# MB_RELAY.net
KiCad netlist of a schematic drawn in Altium Designer
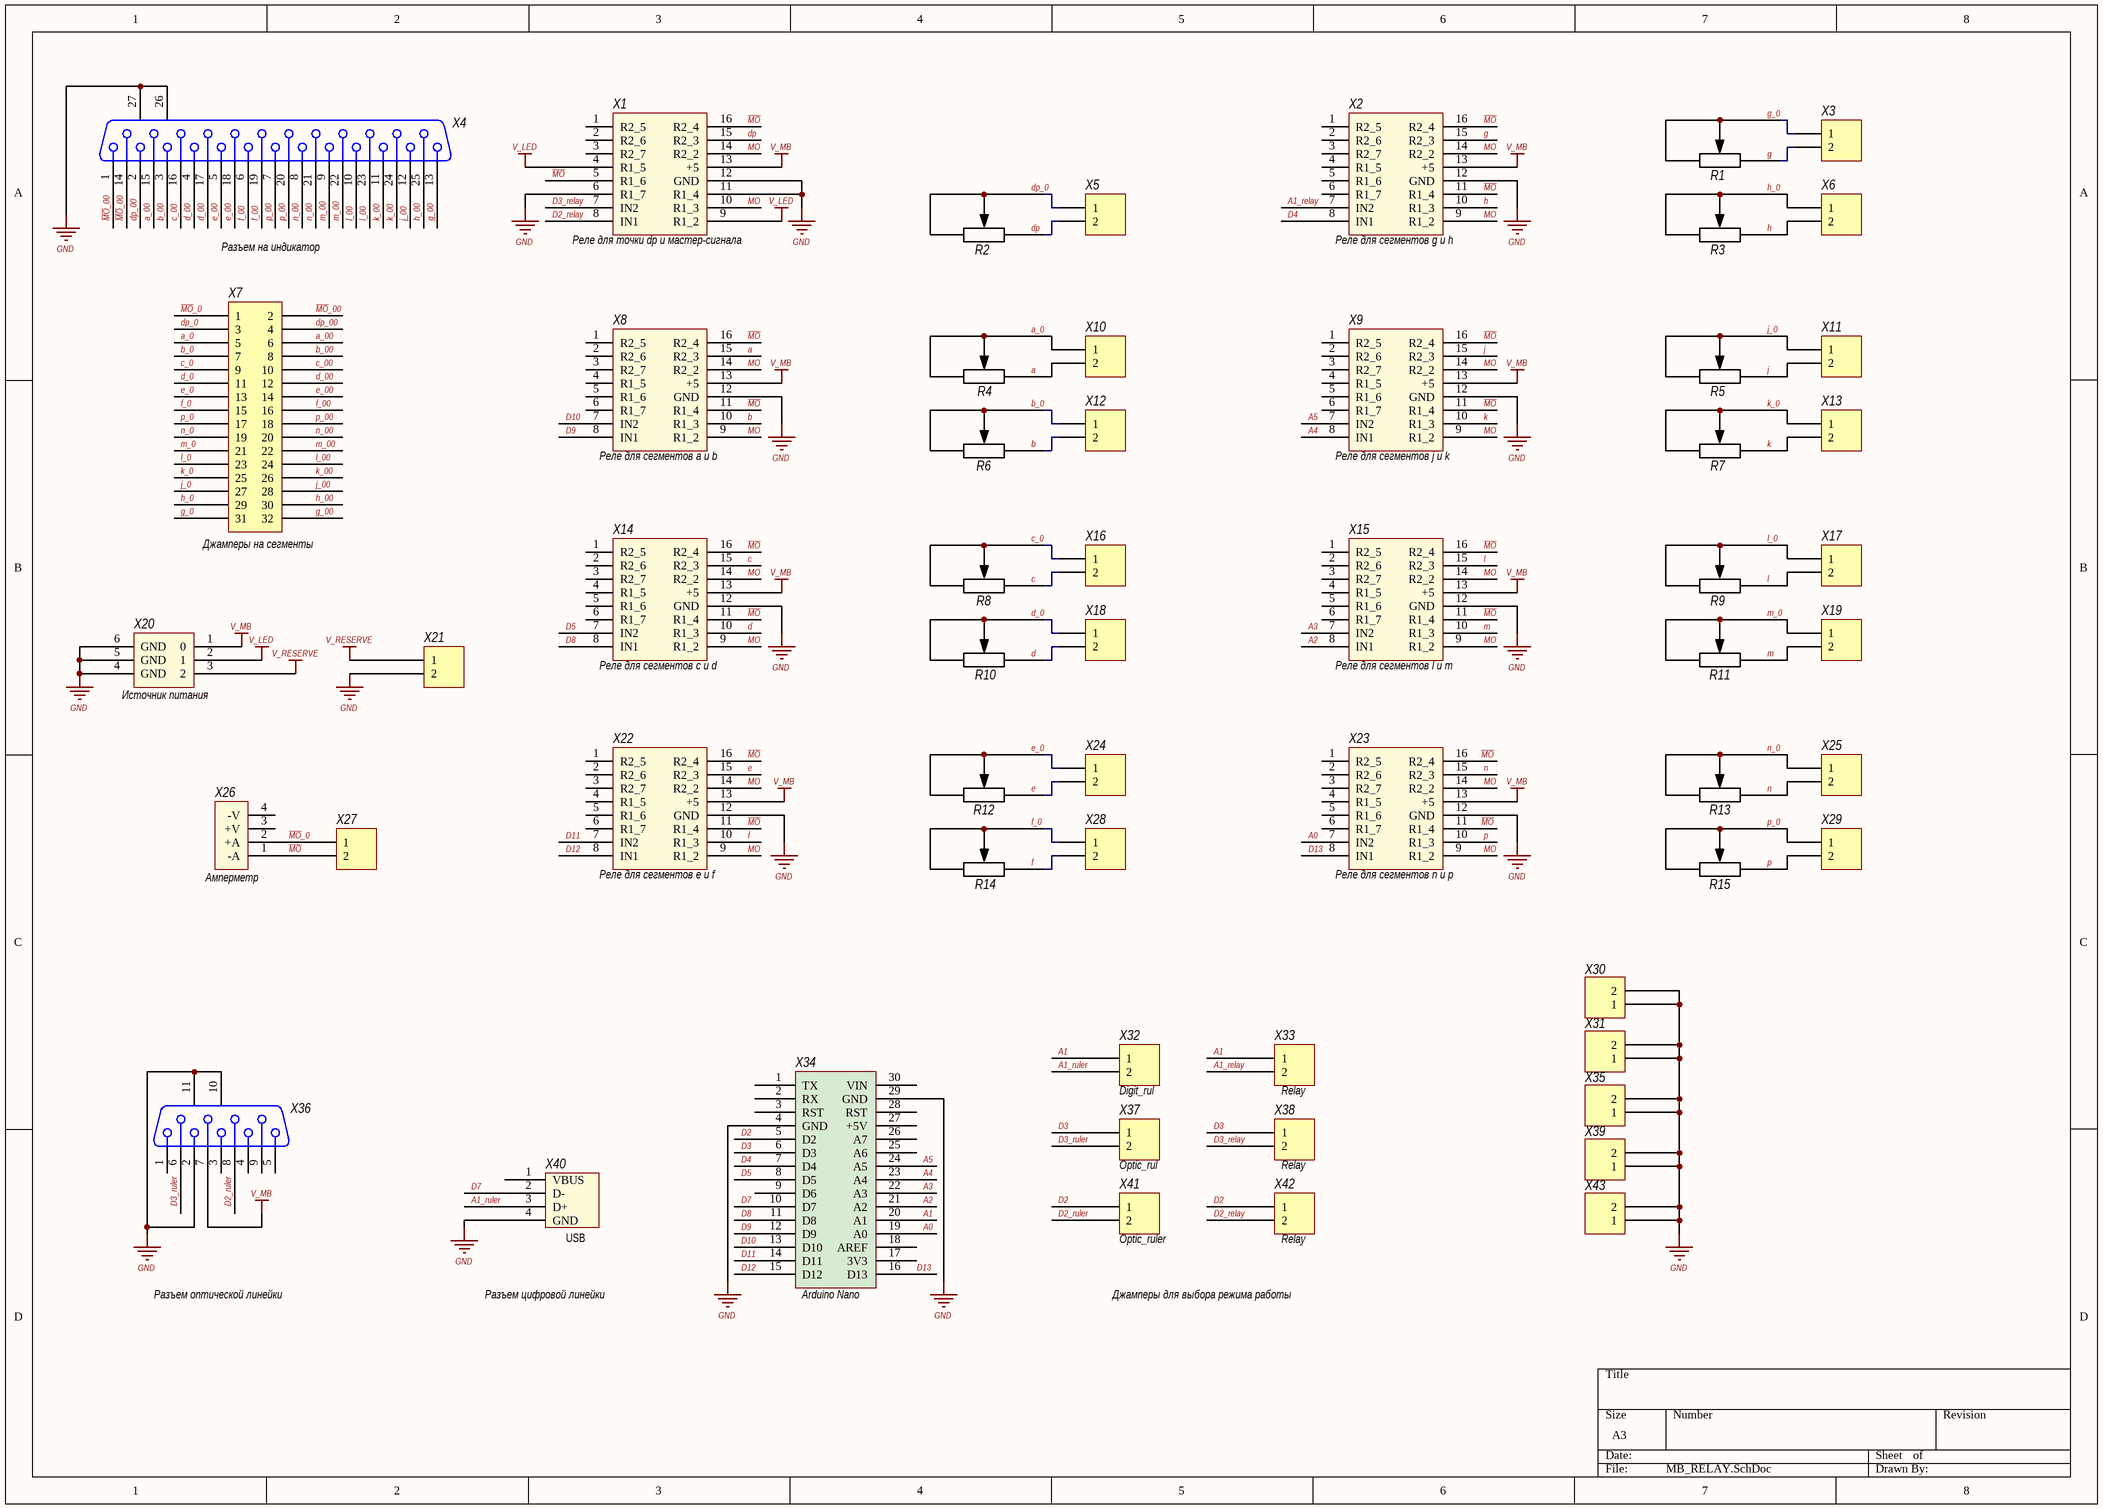
[diagram p0: MB_RELAY.SchDoc]

(export (version "E")
  (design (tool "Eeschema 10.0.6"))
  (components
    (comp (ref "R1")
      (value "RES 3266W")
      (footprint "aab_Passive:RES 3266W")
      (libsource (lib "aab_Schlib") (part "RES 3266W"))
    )
    (comp (ref "R2")
      (value "RES 3266W")
      (footprint "aab_Passive:RES 3266W")
      (libsource (lib "aab_Schlib") (part "RES 3266W"))
    )
    (comp (ref "R3")
      (value "RES 3266W")
      (footprint "aab_Passive:RES 3266W")
      (libsource (lib "aab_Schlib") (part "RES 3266W"))
    )
    (comp (ref "R4")
      (value "Переменнный резистор для")
      (footprint "aab_Passive:RES 3266W")
      (libsource (lib "aab_Schlib") (part "RES 3266W"))
    )
    (comp (ref "R5")
      (value "RES 3266W")
      (footprint "aab_Passive:RES 3266W")
      (libsource (lib "aab_Schlib") (part "RES 3266W"))
    )
    (comp (ref "R6")
      (value "RES 3266W")
      (footprint "aab_Passive:RES 3266W")
      (libsource (lib "aab_Schlib") (part "RES 3266W"))
    )
    (comp (ref "R7")
      (value "RES 3266W")
      (footprint "aab_Passive:RES 3266W")
      (libsource (lib "aab_Schlib") (part "RES 3266W"))
    )
    (comp (ref "R8")
      (value "RES 3266W")
      (footprint "aab_Passive:RES 3266W")
      (libsource (lib "aab_Schlib") (part "RES 3266W"))
    )
    (comp (ref "R9")
      (value "RES 3266W")
      (footprint "aab_Passive:RES 3266W")
      (libsource (lib "aab_Schlib") (part "RES 3266W"))
    )
    (comp (ref "R10")
      (value "RES 3266W")
      (footprint "aab_Passive:RES 3266W")
      (libsource (lib "aab_Schlib") (part "RES 3266W"))
    )
    (comp (ref "R11")
      (value "RES 3266W")
      (footprint "aab_Passive:RES 3266W")
      (libsource (lib "aab_Schlib") (part "RES 3266W"))
    )
    (comp (ref "R12")
      (value "RES 3266W")
      (footprint "aab_Passive:RES 3266W")
      (libsource (lib "aab_Schlib") (part "RES 3266W"))
    )
    (comp (ref "R13")
      (value "RES 3266W")
      (footprint "aab_Passive:RES 3266W")
      (libsource (lib "aab_Schlib") (part "RES 3266W"))
    )
    (comp (ref "R14")
      (value "RES 3266W")
      (footprint "aab_Passive:RES 3266W")
      (libsource (lib "aab_Schlib") (part "RES 3266W"))
    )
    (comp (ref "R15")
      (value "RES 3266W")
      (footprint "aab_Passive:RES 3266W")
      (libsource (lib "aab_Schlib") (part "RES 3266W"))
    )
    (comp (ref "X1")
      (value "Реле для точки dp и мастер-сигнала")
      (footprint "MEZ_RELAY")
      (libsource (lib "msp_SchLib") (part "MEZ_RELAY"))
    )
    (comp (ref "X2")
      (value "Реле для сегментов g и h")
      (footprint "MEZ_RELAY")
      (libsource (lib "msp_SchLib") (part "MEZ_RELAY"))
    )
    (comp (ref "X3")
      (value "GND")
      (footprint "HDR1X2")
      (description "Header, 2-Pin")
      (fields (field (name "PUBLISHER") "Altium Limited"))
      (libsource (lib "Miscellaneous Connectors") (part "Header 2"))
    )
    (comp (ref "X4")
      (value "D Connector 25")
      (footprint "DSUB1.385-2H25A")
      (description "Receptacle Assembly, 25 Position, Right Angle")
      (fields (field (name "PUBLISHER") "Altium Limited"))
      (libsource (lib "Miscellaneous Connectors") (part "D Connector 25"))
    )
    (comp (ref "X5")
      (value "GND")
      (footprint "HDR1X2")
      (description "Header, 2-Pin")
      (fields (field (name "PUBLISHER") "Altium Limited"))
      (libsource (lib "Miscellaneous Connectors") (part "Header 2"))
    )
    (comp (ref "X6")
      (value "GND")
      (footprint "HDR1X2")
      (description "Header, 2-Pin")
      (fields (field (name "PUBLISHER") "Altium Limited"))
      (libsource (lib "Miscellaneous Connectors") (part "Header 2"))
    )
    (comp (ref "X7")
      (value "Header 16X2")
      (footprint "HDR2X16")
      (description "Header, 16-Pin, Dual row")
      (fields (field (name "PUBLISHER") "Altium Limited"))
      (libsource (lib "Miscellaneous Connectors") (part "Header 16X2"))
    )
    (comp (ref "X8")
      (value "Реле для сегментов a и b")
      (footprint "MEZ_RELAY")
      (libsource (lib "msp_SchLib") (part "MEZ_RELAY"))
    )
    (comp (ref "X9")
      (value "Реле для сегментов j и k")
      (footprint "MEZ_RELAY")
      (libsource (lib "msp_SchLib") (part "MEZ_RELAY"))
    )
    (comp (ref "X10")
      (value "Header 2")
      (footprint "HDR1X2")
      (description "Header, 2-Pin")
      (fields (field (name "PUBLISHER") "Altium Limited"))
      (libsource (lib "Miscellaneous Connectors") (part "Header 2"))
    )
    (comp (ref "X11")
      (value "Header 2")
      (footprint "HDR1X2")
      (description "Header, 2-Pin")
      (fields (field (name "PUBLISHER") "Altium Limited"))
      (libsource (lib "Miscellaneous Connectors") (part "Header 2"))
    )
    (comp (ref "X12")
      (value "Header 2")
      (footprint "HDR1X2")
      (description "Header, 2-Pin")
      (fields (field (name "PUBLISHER") "Altium Limited"))
      (libsource (lib "Miscellaneous Connectors") (part "Header 2"))
    )
    (comp (ref "X13")
      (value "Header 2")
      (footprint "HDR1X2")
      (description "Header, 2-Pin")
      (fields (field (name "PUBLISHER") "Altium Limited"))
      (libsource (lib "Miscellaneous Connectors") (part "Header 2"))
    )
    (comp (ref "X14")
      (value "Реле для сегментов c и d")
      (footprint "MEZ_RELAY")
      (libsource (lib "msp_SchLib") (part "MEZ_RELAY"))
    )
    (comp (ref "X15")
      (value "Реле для сегментов l и m")
      (footprint "MEZ_RELAY")
      (libsource (lib "msp_SchLib") (part "MEZ_RELAY"))
    )
    (comp (ref "X16")
      (value "Header 2")
      (footprint "HDR1X2")
      (description "Header, 2-Pin")
      (fields (field (name "PUBLISHER") "Altium Limited"))
      (libsource (lib "Miscellaneous Connectors") (part "Header 2"))
    )
    (comp (ref "X17")
      (value "GND")
      (footprint "HDR1X2")
      (description "Header, 2-Pin")
      (fields (field (name "PUBLISHER") "Altium Limited"))
      (libsource (lib "Miscellaneous Connectors") (part "Header 2"))
    )
    (comp (ref "X18")
      (value "Header 2")
      (footprint "HDR1X2")
      (description "Header, 2-Pin")
      (fields (field (name "PUBLISHER") "Altium Limited"))
      (libsource (lib "Miscellaneous Connectors") (part "Header 2"))
    )
    (comp (ref "X19")
      (value "GND")
      (footprint "HDR1X2")
      (description "Header, 2-Pin")
      (fields (field (name "PUBLISHER") "Altium Limited"))
      (libsource (lib "Miscellaneous Connectors") (part "Header 2"))
    )
    (comp (ref "X20")
      (value "Источник питания")
      (footprint "vpl_Passive:POWER")
      (libsource (lib "msp_SchLib") (part "POWER"))
    )
    (comp (ref "X21")
      (value "Header 2")
      (footprint "HDR1X2")
      (description "Header, 2-Pin")
      (fields (field (name "PUBLISHER") "Altium Limited"))
      (libsource (lib "Miscellaneous Connectors") (part "Header 2"))
    )
    (comp (ref "X22")
      (value "Реле для сегментов e и f")
      (footprint "MEZ_RELAY")
      (libsource (lib "msp_SchLib") (part "MEZ_RELAY"))
    )
    (comp (ref "X23")
      (value "Реле для сегментов n и p")
      (footprint "MEZ_RELAY")
      (libsource (lib "msp_SchLib") (part "MEZ_RELAY"))
    )
    (comp (ref "X24")
      (value "GND")
      (footprint "HDR1X2")
      (description "Header, 2-Pin")
      (fields (field (name "PUBLISHER") "Altium Limited"))
      (libsource (lib "Miscellaneous Connectors") (part "Header 2"))
    )
    (comp (ref "X25")
      (value "GND")
      (footprint "HDR1X2")
      (description "Header, 2-Pin")
      (fields (field (name "PUBLISHER") "Altium Limited"))
      (libsource (lib "Miscellaneous Connectors") (part "Header 2"))
    )
    (comp (ref "X26")
      (value "Амперметр")
      (footprint "vpl_Passive:AMP_VOLTMETER")
      (libsource (lib "msp_SchLib") (part "AMP_VOLTMETR"))
    )
    (comp (ref "X27")
      (value "Header 2")
      (footprint "HDR1X2")
      (description "Header, 2-Pin")
      (fields (field (name "PUBLISHER") "Altium Limited"))
      (libsource (lib "Miscellaneous Connectors") (part "Header 2"))
    )
    (comp (ref "X28")
      (value "GND")
      (footprint "HDR1X2")
      (description "Header, 2-Pin")
      (fields (field (name "PUBLISHER") "Altium Limited"))
      (libsource (lib "Miscellaneous Connectors") (part "Header 2"))
    )
    (comp (ref "X29")
      (value "GND")
      (footprint "HDR1X2")
      (description "Header, 2-Pin")
      (fields (field (name "PUBLISHER") "Altium Limited"))
      (libsource (lib "Miscellaneous Connectors") (part "Header 2"))
    )
    (comp (ref "X30")
      (value "Header 2")
      (footprint "HDR1X2")
      (description "Header, 2-Pin")
      (fields (field (name "PUBLISHER") "Altium Limited"))
      (libsource (lib "") (part "Header 2_1"))
    )
    (comp (ref "X31")
      (value "GND")
      (footprint "HDR1X2")
      (description "Header, 2-Pin")
      (fields (field (name "PUBLISHER") "Altium Limited"))
      (libsource (lib "") (part "Header 2_1"))
    )
    (comp (ref "X32")
      (value "Digit_rul")
      (footprint "HDR1X2")
      (description "Header, 2-Pin")
      (fields (field (name "PUBLISHER") "Altium Limited"))
      (libsource (lib "Miscellaneous Connectors") (part "Header 2"))
    )
    (comp (ref "X33")
      (value "Relay")
      (footprint "HDR1X2")
      (description "Header, 2-Pin")
      (fields (field (name "PUBLISHER") "Altium Limited"))
      (libsource (lib "Miscellaneous Connectors") (part "Header 2"))
    )
    (comp (ref "X34")
      (value "Arduino Nano")
      (footprint "PCBComponent_1")
      (libsource (lib "Nano") (part "Component_1"))
    )
    (comp (ref "X35")
      (value "GND")
      (footprint "HDR1X2")
      (description "Header, 2-Pin")
      (fields (field (name "PUBLISHER") "Altium Limited"))
      (libsource (lib "") (part "Header 2_1"))
    )
    (comp (ref "X36")
      (value "D Connector 9")
      (footprint "DSUB1.385-2H9")
      (description "Receptacle Assembly, 9 Position, Right Angle")
      (fields (field (name "PUBLISHER") "Altium Limited"))
      (libsource (lib "Miscellaneous Connectors") (part "D Connector 9"))
    )
    (comp (ref "X37")
      (value "Optic_rul")
      (footprint "HDR1X2")
      (description "Header, 2-Pin")
      (fields (field (name "PUBLISHER") "Altium Limited"))
      (libsource (lib "Miscellaneous Connectors") (part "Header 2"))
    )
    (comp (ref "X38")
      (value "Relay")
      (footprint "HDR1X2")
      (description "Header, 2-Pin")
      (fields (field (name "PUBLISHER") "Altium Limited"))
      (libsource (lib "Miscellaneous Connectors") (part "Header 2"))
    )
    (comp (ref "X39")
      (value "GND")
      (footprint "HDR1X2")
      (description "Header, 2-Pin")
      (fields (field (name "PUBLISHER") "Altium Limited"))
      (libsource (lib "") (part "Header 2_1"))
    )
    (comp (ref "X40") (value "USB") (footprint "USB") (libsource (lib "msp_SchLib") (part "USB")))
    (comp (ref "X41")
      (value "Optic_ruler")
      (footprint "HDR1X2")
      (description "Header, 2-Pin")
      (fields (field (name "PUBLISHER") "Altium Limited"))
      (libsource (lib "Miscellaneous Connectors") (part "Header 2"))
    )
    (comp (ref "X42")
      (value "Relay")
      (footprint "HDR1X2")
      (description "Header, 2-Pin")
      (fields (field (name "PUBLISHER") "Altium Limited"))
      (libsource (lib "Miscellaneous Connectors") (part "Header 2"))
    )
    (comp (ref "X43")
      (value "GND")
      (footprint "HDR1X2")
      (description "Header, 2-Pin")
      (fields (field (name "PUBLISHER") "Altium Limited"))
      (libsource (lib "") (part "Header 2_1"))
    )
  )
  (nets
    (net (code "1") (name "/A0") (class "Default")
      (node (ref "X23") (pin "7") (pinfunction "IN2_7") (pintype "passive"))
      (node (ref "X34") (pin "19") (pinfunction "A0_19") (pintype "passive"))
    )
    (net (code "2") (name "/A1") (class "Default")
      (node (ref "X32") (pin "1") (pinfunction "1_1") (pintype "passive"))
      (node (ref "X33") (pin "1") (pinfunction "1_1") (pintype "passive"))
      (node (ref "X34") (pin "20") (pinfunction "A1_20") (pintype "passive"))
    )
    (net (code "3") (name "/A1_relay") (class "Default")
      (node (ref "X2") (pin "7") (pinfunction "IN2_7") (pintype "passive"))
      (node (ref "X33") (pin "2") (pinfunction "2_2") (pintype "passive"))
    )
    (net (code "4") (name "/A1_ruler") (class "Default")
      (node (ref "X32") (pin "2") (pinfunction "2_2") (pintype "passive"))
      (node (ref "X40") (pin "3") (pinfunction "D+_3") (pintype "passive"))
    )
    (net (code "5") (name "/A2") (class "Default")
      (node (ref "X15") (pin "8") (pinfunction "IN1_8") (pintype "passive"))
      (node (ref "X34") (pin "21") (pinfunction "A2_21") (pintype "passive"))
    )
    (net (code "6") (name "/A3") (class "Default")
      (node (ref "X15") (pin "7") (pinfunction "IN2_7") (pintype "passive"))
      (node (ref "X34") (pin "22") (pinfunction "A3_22") (pintype "passive"))
    )
    (net (code "7") (name "/A4") (class "Default")
      (node (ref "X34") (pin "23") (pinfunction "A4_23") (pintype "passive"))
      (node (ref "X9") (pin "8") (pinfunction "IN1_8") (pintype "passive"))
    )
    (net (code "8") (name "/A5") (class "Default")
      (node (ref "X34") (pin "24") (pinfunction "A5_24") (pintype "passive"))
      (node (ref "X9") (pin "7") (pinfunction "IN2_7") (pintype "passive"))
    )
    (net (code "9") (name "/D2") (class "Default")
      (node (ref "X34") (pin "5") (pinfunction "D2_5") (pintype "passive"))
      (node (ref "X41") (pin "1") (pinfunction "1_1") (pintype "passive"))
      (node (ref "X42") (pin "1") (pinfunction "1_1") (pintype "passive"))
    )
    (net (code "10") (name "/D2_relay") (class "Default")
      (node (ref "X1") (pin "8") (pinfunction "IN1_8") (pintype "passive"))
      (node (ref "X42") (pin "2") (pinfunction "2_2") (pintype "passive"))
    )
    (net (code "11") (name "/D2_ruler") (class "Default")
      (node (ref "X36") (pin "8") (pinfunction "8_8") (pintype "passive"))
      (node (ref "X41") (pin "2") (pinfunction "2_2") (pintype "passive"))
    )
    (net (code "12") (name "/D3") (class "Default")
      (node (ref "X34") (pin "6") (pinfunction "D3_6") (pintype "passive"))
      (node (ref "X37") (pin "1") (pinfunction "1_1") (pintype "passive"))
      (node (ref "X38") (pin "1") (pinfunction "1_1") (pintype "passive"))
    )
    (net (code "13") (name "/D3_relay") (class "Default")
      (node (ref "X1") (pin "7") (pinfunction "IN2_7") (pintype "passive"))
      (node (ref "X38") (pin "2") (pinfunction "2_2") (pintype "passive"))
    )
    (net (code "14") (name "/D3_ruler") (class "Default")
      (node (ref "X36") (pin "6") (pinfunction "6_6") (pintype "passive"))
      (node (ref "X37") (pin "2") (pinfunction "2_2") (pintype "passive"))
    )
    (net (code "15") (name "/D4") (class "Default")
      (node (ref "X2") (pin "8") (pinfunction "IN1_8") (pintype "passive"))
      (node (ref "X34") (pin "7") (pinfunction "D4_7") (pintype "passive"))
    )
    (net (code "16") (name "/D5") (class "Default")
      (node (ref "X14") (pin "7") (pinfunction "IN2_7") (pintype "passive"))
      (node (ref "X34") (pin "8") (pinfunction "D5_8") (pintype "passive"))
    )
    (net (code "17") (name "/D7") (class "Default")
      (node (ref "X34") (pin "10") (pinfunction "D7_10") (pintype "passive"))
      (node (ref "X40") (pin "2") (pinfunction "D-_2") (pintype "passive"))
    )
    (net (code "18") (name "/D8") (class "Default")
      (node (ref "X14") (pin "8") (pinfunction "IN1_8") (pintype "passive"))
      (node (ref "X34") (pin "11") (pinfunction "D8_11") (pintype "passive"))
    )
    (net (code "19") (name "/D9") (class "Default")
      (node (ref "X34") (pin "12") (pinfunction "D9_12") (pintype "passive"))
      (node (ref "X8") (pin "8") (pinfunction "IN1_8") (pintype "passive"))
    )
    (net (code "20") (name "/D10") (class "Default")
      (node (ref "X34") (pin "13") (pinfunction "D10_13") (pintype "passive"))
      (node (ref "X8") (pin "7") (pinfunction "IN2_7") (pintype "passive"))
    )
    (net (code "21") (name "/D11") (class "Default")
      (node (ref "X22") (pin "7") (pinfunction "IN2_7") (pintype "passive"))
      (node (ref "X34") (pin "14") (pinfunction "D11_14") (pintype "passive"))
    )
    (net (code "22") (name "/D12") (class "Default")
      (node (ref "X22") (pin "8") (pinfunction "IN1_8") (pintype "passive"))
      (node (ref "X34") (pin "15") (pinfunction "D12_15") (pintype "passive"))
    )
    (net (code "23") (name "/D13") (class "Default")
      (node (ref "X23") (pin "8") (pinfunction "IN1_8") (pintype "passive"))
      (node (ref "X34") (pin "16") (pinfunction "D13_16") (pintype "passive"))
    )
    (net (code "24") (name "/MO") (class "Default")
      (node (ref "X1") (pin "10") (pinfunction "R1_3_10") (pintype "passive"))
      (node (ref "X1") (pin "14") (pinfunction "R2_2_14") (pintype "passive"))
      (node (ref "X14") (pin "14") (pinfunction "R2_2_14") (pintype "passive"))
      (node (ref "X14") (pin "9") (pinfunction "R1_2_9") (pintype "passive"))
      (node (ref "X15") (pin "14") (pinfunction "R2_2_14") (pintype "passive"))
      (node (ref "X15") (pin "9") (pinfunction "R1_2_9") (pintype "passive"))
      (node (ref "X2") (pin "14") (pinfunction "R2_2_14") (pintype "passive"))
      (node (ref "X2") (pin "9") (pinfunction "R1_2_9") (pintype "passive"))
      (node (ref "X22") (pin "14") (pinfunction "R2_2_14") (pintype "passive"))
      (node (ref "X22") (pin "9") (pinfunction "R1_2_9") (pintype "passive"))
      (node (ref "X23") (pin "14") (pinfunction "R2_2_14") (pintype "passive"))
      (node (ref "X23") (pin "9") (pinfunction "R1_2_9") (pintype "passive"))
      (node (ref "X8") (pin "14") (pinfunction "R2_2_14") (pintype "passive"))
      (node (ref "X8") (pin "9") (pinfunction "R1_2_9") (pintype "passive"))
      (node (ref "X9") (pin "14") (pinfunction "R2_2_14") (pintype "passive"))
      (node (ref "X9") (pin "9") (pinfunction "R1_2_9") (pintype "passive"))
    )
    (net (code "25") (name "/a") (class "Default")
      (node (ref "R4") (pin "3") (pinfunction "3_3") (pintype "passive"))
      (node (ref "X10") (pin "2") (pinfunction "2_2") (pintype "passive"))
      (node (ref "X8") (pin "15") (pinfunction "R2_3_15") (pintype "passive"))
    )
    (net (code "26") (name "/a_00") (class "Default")
      (node (ref "X4") (pin "15") (pinfunction "15_15") (pintype "passive"))
      (node (ref "X7") (pin "6") (pinfunction "6_6") (pintype "passive"))
    )
    (net (code "27") (name "/a_0") (class "Default")
      (node (ref "R4") (pin "1") (pinfunction "1_1") (pintype "passive"))
      (node (ref "R4") (pin "2") (pinfunction "2_2") (pintype "passive"))
      (node (ref "X10") (pin "1") (pinfunction "1_1") (pintype "passive"))
      (node (ref "X7") (pin "5") (pinfunction "5_5") (pintype "passive"))
    )
    (net (code "28") (name "/b") (class "Default")
      (node (ref "R6") (pin "3") (pinfunction "3_3") (pintype "passive"))
      (node (ref "X12") (pin "2") (pinfunction "2_2") (pintype "passive"))
      (node (ref "X8") (pin "10") (pinfunction "R1_3_10") (pintype "passive"))
    )
    (net (code "29") (name "/b_00") (class "Default")
      (node (ref "X4") (pin "3") (pinfunction "3_3") (pintype "passive"))
      (node (ref "X7") (pin "8") (pinfunction "8_8") (pintype "passive"))
    )
    (net (code "30") (name "/b_0") (class "Default")
      (node (ref "R6") (pin "1") (pinfunction "1_1") (pintype "passive"))
      (node (ref "R6") (pin "2") (pinfunction "2_2") (pintype "passive"))
      (node (ref "X12") (pin "1") (pinfunction "1_1") (pintype "passive"))
      (node (ref "X7") (pin "7") (pinfunction "7_7") (pintype "passive"))
    )
    (net (code "31") (name "/c") (class "Default")
      (node (ref "R8") (pin "3") (pinfunction "3_3") (pintype "passive"))
      (node (ref "X14") (pin "15") (pinfunction "R2_3_15") (pintype "passive"))
      (node (ref "X16") (pin "2") (pinfunction "2_2") (pintype "passive"))
    )
    (net (code "32") (name "/c_00") (class "Default")
      (node (ref "X4") (pin "16") (pinfunction "16_16") (pintype "passive"))
      (node (ref "X7") (pin "10") (pinfunction "10_10") (pintype "passive"))
    )
    (net (code "33") (name "/c_0") (class "Default")
      (node (ref "R8") (pin "1") (pinfunction "1_1") (pintype "passive"))
      (node (ref "R8") (pin "2") (pinfunction "2_2") (pintype "passive"))
      (node (ref "X16") (pin "1") (pinfunction "1_1") (pintype "passive"))
      (node (ref "X7") (pin "9") (pinfunction "9_9") (pintype "passive"))
    )
    (net (code "34") (name "/d") (class "Default")
      (node (ref "R10") (pin "3") (pinfunction "3_3") (pintype "passive"))
      (node (ref "X14") (pin "10") (pinfunction "R1_3_10") (pintype "passive"))
      (node (ref "X18") (pin "2") (pinfunction "2_2") (pintype "passive"))
    )
    (net (code "35") (name "/d_0") (class "Default")
      (node (ref "R10") (pin "1") (pinfunction "1_1") (pintype "passive"))
      (node (ref "R10") (pin "2") (pinfunction "2_2") (pintype "passive"))
      (node (ref "X18") (pin "1") (pinfunction "1_1") (pintype "passive"))
      (node (ref "X7") (pin "11") (pinfunction "11_11") (pintype "passive"))
    )
    (net (code "36") (name "/d_00") (class "Default")
      (node (ref "X4") (pin "17") (pinfunction "17_17") (pintype "passive"))
      (node (ref "X4") (pin "4") (pinfunction "4_4") (pintype "passive"))
      (node (ref "X7") (pin "12") (pinfunction "12_12") (pintype "passive"))
    )
    (net (code "37") (name "/dp") (class "Default")
      (node (ref "R2") (pin "3") (pinfunction "3_3") (pintype "passive"))
      (node (ref "X1") (pin "15") (pinfunction "R2_3_15") (pintype "passive"))
      (node (ref "X5") (pin "2") (pinfunction "2_2") (pintype "passive"))
    )
    (net (code "38") (name "/dp_00") (class "Default")
      (node (ref "X4") (pin "2") (pinfunction "2_2") (pintype "passive"))
      (node (ref "X7") (pin "4") (pinfunction "4_4") (pintype "passive"))
    )
    (net (code "39") (name "/dp_0") (class "Default")
      (node (ref "R2") (pin "1") (pinfunction "1_1") (pintype "passive"))
      (node (ref "R2") (pin "2") (pinfunction "2_2") (pintype "passive"))
      (node (ref "X5") (pin "1") (pinfunction "1_1") (pintype "passive"))
      (node (ref "X7") (pin "3") (pinfunction "3_3") (pintype "passive"))
    )
    (net (code "40") (name "/e") (class "Default")
      (node (ref "R12") (pin "3") (pinfunction "3_3") (pintype "passive"))
      (node (ref "X22") (pin "15") (pinfunction "R2_3_15") (pintype "passive"))
      (node (ref "X24") (pin "2") (pinfunction "2_2") (pintype "passive"))
    )
    (net (code "41") (name "/e_0") (class "Default")
      (node (ref "R12") (pin "1") (pinfunction "1_1") (pintype "passive"))
      (node (ref "R12") (pin "2") (pinfunction "2_2") (pintype "passive"))
      (node (ref "X24") (pin "1") (pinfunction "1_1") (pintype "passive"))
      (node (ref "X7") (pin "13") (pinfunction "13_13") (pintype "passive"))
    )
    (net (code "42") (name "/e_00") (class "Default")
      (node (ref "X4") (pin "18") (pinfunction "18_18") (pintype "passive"))
      (node (ref "X4") (pin "5") (pinfunction "5_5") (pintype "passive"))
      (node (ref "X7") (pin "14") (pinfunction "14_14") (pintype "passive"))
    )
    (net (code "43") (name "/f") (class "Default")
      (node (ref "R14") (pin "3") (pinfunction "3_3") (pintype "passive"))
      (node (ref "X22") (pin "10") (pinfunction "R1_3_10") (pintype "passive"))
      (node (ref "X28") (pin "2") (pinfunction "2_2") (pintype "passive"))
    )
    (net (code "44") (name "/f_0") (class "Default")
      (node (ref "R14") (pin "1") (pinfunction "1_1") (pintype "passive"))
      (node (ref "R14") (pin "2") (pinfunction "2_2") (pintype "passive"))
      (node (ref "X28") (pin "1") (pinfunction "1_1") (pintype "passive"))
      (node (ref "X7") (pin "15") (pinfunction "15_15") (pintype "passive"))
    )
    (net (code "45") (name "/f_00") (class "Default")
      (node (ref "X4") (pin "19") (pinfunction "19_19") (pintype "passive"))
      (node (ref "X4") (pin "6") (pinfunction "6_6") (pintype "passive"))
      (node (ref "X7") (pin "16") (pinfunction "16_16") (pintype "passive"))
    )
    (net (code "46") (name "/g") (class "Default")
      (node (ref "R1") (pin "3") (pinfunction "3_3") (pintype "passive"))
      (node (ref "X2") (pin "15") (pinfunction "R2_3_15") (pintype "passive"))
      (node (ref "X3") (pin "2") (pinfunction "2_2") (pintype "passive"))
    )
    (net (code "47") (name "/g_0") (class "Default")
      (node (ref "R1") (pin "1") (pinfunction "1_1") (pintype "passive"))
      (node (ref "R1") (pin "2") (pinfunction "2_2") (pintype "passive"))
      (node (ref "X3") (pin "1") (pinfunction "1_1") (pintype "passive"))
      (node (ref "X7") (pin "31") (pinfunction "31_31") (pintype "passive"))
    )
    (net (code "48") (name "/g_00") (class "Default")
      (node (ref "X4") (pin "13") (pinfunction "13_13") (pintype "passive"))
      (node (ref "X7") (pin "32") (pinfunction "32_32") (pintype "passive"))
    )
    (net (code "49") (name "/h") (class "Default")
      (node (ref "R3") (pin "3") (pinfunction "3_3") (pintype "passive"))
      (node (ref "X2") (pin "10") (pinfunction "R1_3_10") (pintype "passive"))
      (node (ref "X6") (pin "2") (pinfunction "2_2") (pintype "passive"))
    )
    (net (code "50") (name "/h_0") (class "Default")
      (node (ref "R3") (pin "1") (pinfunction "1_1") (pintype "passive"))
      (node (ref "R3") (pin "2") (pinfunction "2_2") (pintype "passive"))
      (node (ref "X6") (pin "1") (pinfunction "1_1") (pintype "passive"))
      (node (ref "X7") (pin "29") (pinfunction "29_29") (pintype "passive"))
    )
    (net (code "51") (name "/h_00") (class "Default")
      (node (ref "X4") (pin "25") (pinfunction "25_25") (pintype "passive"))
      (node (ref "X7") (pin "30") (pinfunction "30_30") (pintype "passive"))
    )
    (net (code "52") (name "/j") (class "Default")
      (node (ref "R5") (pin "3") (pinfunction "3_3") (pintype "passive"))
      (node (ref "X11") (pin "2") (pinfunction "2_2") (pintype "passive"))
      (node (ref "X9") (pin "15") (pinfunction "R2_3_15") (pintype "passive"))
    )
    (net (code "53") (name "/j_00") (class "Default")
      (node (ref "X4") (pin "12") (pinfunction "12_12") (pintype "passive"))
      (node (ref "X7") (pin "28") (pinfunction "28_28") (pintype "passive"))
    )
    (net (code "54") (name "/j_0") (class "Default")
      (node (ref "R5") (pin "1") (pinfunction "1_1") (pintype "passive"))
      (node (ref "R5") (pin "2") (pinfunction "2_2") (pintype "passive"))
      (node (ref "X11") (pin "1") (pinfunction "1_1") (pintype "passive"))
      (node (ref "X7") (pin "27") (pinfunction "27_27") (pintype "passive"))
    )
    (net (code "55") (name "/k") (class "Default")
      (node (ref "R7") (pin "3") (pinfunction "3_3") (pintype "passive"))
      (node (ref "X13") (pin "2") (pinfunction "2_2") (pintype "passive"))
      (node (ref "X9") (pin "10") (pinfunction "R1_3_10") (pintype "passive"))
    )
    (net (code "56") (name "/k_00") (class "Default")
      (node (ref "X4") (pin "11") (pinfunction "11_11") (pintype "passive"))
      (node (ref "X4") (pin "24") (pinfunction "24_24") (pintype "passive"))
      (node (ref "X7") (pin "26") (pinfunction "26_26") (pintype "passive"))
    )
    (net (code "57") (name "/k_0") (class "Default")
      (node (ref "R7") (pin "1") (pinfunction "1_1") (pintype "passive"))
      (node (ref "R7") (pin "2") (pinfunction "2_2") (pintype "passive"))
      (node (ref "X13") (pin "1") (pinfunction "1_1") (pintype "passive"))
      (node (ref "X7") (pin "25") (pinfunction "25_25") (pintype "passive"))
    )
    (net (code "58") (name "/l") (class "Default")
      (node (ref "R9") (pin "3") (pinfunction "3_3") (pintype "passive"))
      (node (ref "X15") (pin "15") (pinfunction "R2_3_15") (pintype "passive"))
      (node (ref "X17") (pin "2") (pinfunction "2_2") (pintype "passive"))
    )
    (net (code "59") (name "/l_00") (class "Default")
      (node (ref "X4") (pin "10") (pinfunction "10_10") (pintype "passive"))
      (node (ref "X4") (pin "23") (pinfunction "23_23") (pintype "passive"))
      (node (ref "X7") (pin "24") (pinfunction "24_24") (pintype "passive"))
    )
    (net (code "60") (name "/l_0") (class "Default")
      (node (ref "R9") (pin "1") (pinfunction "1_1") (pintype "passive"))
      (node (ref "R9") (pin "2") (pinfunction "2_2") (pintype "passive"))
      (node (ref "X17") (pin "1") (pinfunction "1_1") (pintype "passive"))
      (node (ref "X7") (pin "23") (pinfunction "23_23") (pintype "passive"))
    )
    (net (code "61") (name "/m") (class "Default")
      (node (ref "R11") (pin "3") (pinfunction "3_3") (pintype "passive"))
      (node (ref "X15") (pin "10") (pinfunction "R1_3_10") (pintype "passive"))
      (node (ref "X19") (pin "2") (pinfunction "2_2") (pintype "passive"))
    )
    (net (code "62") (name "/m_00") (class "Default")
      (node (ref "X4") (pin "22") (pinfunction "22_22") (pintype "passive"))
      (node (ref "X4") (pin "9") (pinfunction "9_9") (pintype "passive"))
      (node (ref "X7") (pin "22") (pinfunction "22_22") (pintype "passive"))
    )
    (net (code "63") (name "/m_0") (class "Default")
      (node (ref "R11") (pin "1") (pinfunction "1_1") (pintype "passive"))
      (node (ref "R11") (pin "2") (pinfunction "2_2") (pintype "passive"))
      (node (ref "X19") (pin "1") (pinfunction "1_1") (pintype "passive"))
      (node (ref "X7") (pin "21") (pinfunction "21_21") (pintype "passive"))
    )
    (net (code "64") (name "/n") (class "Default")
      (node (ref "R13") (pin "3") (pinfunction "3_3") (pintype "passive"))
      (node (ref "X23") (pin "15") (pinfunction "R2_3_15") (pintype "passive"))
      (node (ref "X25") (pin "2") (pinfunction "2_2") (pintype "passive"))
    )
    (net (code "65") (name "/n_00") (class "Default")
      (node (ref "X4") (pin "21") (pinfunction "21_21") (pintype "passive"))
      (node (ref "X4") (pin "8") (pinfunction "8_8") (pintype "passive"))
      (node (ref "X7") (pin "20") (pinfunction "20_20") (pintype "passive"))
    )
    (net (code "66") (name "/n_0") (class "Default")
      (node (ref "R13") (pin "1") (pinfunction "1_1") (pintype "passive"))
      (node (ref "R13") (pin "2") (pinfunction "2_2") (pintype "passive"))
      (node (ref "X25") (pin "1") (pinfunction "1_1") (pintype "passive"))
      (node (ref "X7") (pin "19") (pinfunction "19_19") (pintype "passive"))
    )
    (net (code "67") (name "/p") (class "Default")
      (node (ref "R15") (pin "3") (pinfunction "3_3") (pintype "passive"))
      (node (ref "X23") (pin "10") (pinfunction "R1_3_10") (pintype "passive"))
      (node (ref "X29") (pin "2") (pinfunction "2_2") (pintype "passive"))
    )
    (net (code "68") (name "/p_0") (class "Default")
      (node (ref "R15") (pin "1") (pinfunction "1_1") (pintype "passive"))
      (node (ref "R15") (pin "2") (pinfunction "2_2") (pintype "passive"))
      (node (ref "X29") (pin "1") (pinfunction "1_1") (pintype "passive"))
      (node (ref "X7") (pin "17") (pinfunction "17_17") (pintype "passive"))
    )
    (net (code "69") (name "/p_00") (class "Default")
      (node (ref "X4") (pin "20") (pinfunction "20_20") (pintype "passive"))
      (node (ref "X4") (pin "7") (pinfunction "7_7") (pintype "passive"))
      (node (ref "X7") (pin "18") (pinfunction "18_18") (pintype "passive"))
    )
    (net (code "70") (name "/~{MO}") (class "Default")
      (node (ref "X1") (pin "16") (pinfunction "R2_4_16") (pintype "passive"))
      (node (ref "X1") (pin "5") (pinfunction "R1_6_5") (pintype "passive"))
      (node (ref "X14") (pin "11") (pinfunction "R1_4_11") (pintype "passive"))
      (node (ref "X14") (pin "16") (pinfunction "R2_4_16") (pintype "passive"))
      (node (ref "X15") (pin "11") (pinfunction "R1_4_11") (pintype "passive"))
      (node (ref "X15") (pin "16") (pinfunction "R2_4_16") (pintype "passive"))
      (node (ref "X2") (pin "11") (pinfunction "R1_4_11") (pintype "passive"))
      (node (ref "X2") (pin "16") (pinfunction "R2_4_16") (pintype "passive"))
      (node (ref "X22") (pin "11") (pinfunction "R1_4_11") (pintype "passive"))
      (node (ref "X22") (pin "16") (pinfunction "R2_4_16") (pintype "passive"))
      (node (ref "X23") (pin "11") (pinfunction "R1_4_11") (pintype "passive"))
      (node (ref "X23") (pin "16") (pinfunction "R2_4_16") (pintype "passive"))
      (node (ref "X26") (pin "1") (pinfunction "-A_1") (pintype "passive"))
      (node (ref "X27") (pin "2") (pinfunction "2_2") (pintype "passive"))
      (node (ref "X8") (pin "11") (pinfunction "R1_4_11") (pintype "passive"))
      (node (ref "X8") (pin "16") (pinfunction "R2_4_16") (pintype "passive"))
      (node (ref "X9") (pin "11") (pinfunction "R1_4_11") (pintype "passive"))
      (node (ref "X9") (pin "16") (pinfunction "R2_4_16") (pintype "passive"))
    )
    (net (code "71") (name "/~{MO}_0") (class "Default")
      (node (ref "X26") (pin "2") (pinfunction "+A_2") (pintype "passive"))
      (node (ref "X27") (pin "1") (pinfunction "1_1") (pintype "passive"))
      (node (ref "X7") (pin "1") (pinfunction "1_1") (pintype "passive"))
    )
    (net (code "72") (name "/~{MO}_00") (class "Default")
      (node (ref "X4") (pin "1") (pinfunction "1_1") (pintype "passive"))
      (node (ref "X4") (pin "14") (pinfunction "14_14") (pintype "passive"))
      (node (ref "X7") (pin "2") (pinfunction "2_2") (pintype "passive"))
    )
    (net (code "73") (name "GND") (class "Default")
      (node (ref "X1") (pin "11") (pinfunction "R1_4_11") (pintype "passive"))
      (node (ref "X1") (pin "12") (pinfunction "GND_12") (pintype "passive"))
      (node (ref "X1") (pin "6") (pinfunction "R1_7_6") (pintype "passive"))
      (node (ref "X14") (pin "12") (pinfunction "GND_12") (pintype "passive"))
      (node (ref "X15") (pin "12") (pinfunction "GND_12") (pintype "passive"))
      (node (ref "X2") (pin "12") (pinfunction "GND_12") (pintype "passive"))
      (node (ref "X20") (pin "4") (pinfunction "GND_4") (pintype "passive"))
      (node (ref "X20") (pin "5") (pinfunction "GND_5") (pintype "passive"))
      (node (ref "X20") (pin "6") (pinfunction "GND_6") (pintype "passive"))
      (node (ref "X21") (pin "2") (pinfunction "2_2") (pintype "passive"))
      (node (ref "X22") (pin "12") (pinfunction "GND_12") (pintype "passive"))
      (node (ref "X23") (pin "12") (pinfunction "GND_12") (pintype "passive"))
      (node (ref "X30") (pin "1") (pinfunction "1_1") (pintype "passive"))
      (node (ref "X30") (pin "2") (pinfunction "2_2") (pintype "passive"))
      (node (ref "X31") (pin "1") (pinfunction "1_1") (pintype "passive"))
      (node (ref "X31") (pin "2") (pinfunction "2_2") (pintype "passive"))
      (node (ref "X34") (pin "29") (pinfunction "GND_29") (pintype "passive"))
      (node (ref "X34") (pin "4") (pinfunction "GND_4") (pintype "passive"))
      (node (ref "X35") (pin "1") (pinfunction "1_1") (pintype "passive"))
      (node (ref "X35") (pin "2") (pinfunction "2_2") (pintype "passive"))
      (node (ref "X36") (pin "10") (pinfunction "MH1_10") (pintype "passive"))
      (node (ref "X36") (pin "11") (pinfunction "MH2_11") (pintype "passive"))
      (node (ref "X36") (pin "2") (pinfunction "2_2") (pintype "passive"))
      (node (ref "X39") (pin "1") (pinfunction "1_1") (pintype "passive"))
      (node (ref "X39") (pin "2") (pinfunction "2_2") (pintype "passive"))
      (node (ref "X4") (pin "26") (pinfunction "MH1_26") (pintype "passive"))
      (node (ref "X4") (pin "27") (pinfunction "MH2_27") (pintype "passive"))
      (node (ref "X40") (pin "4") (pinfunction "GND_4") (pintype "passive"))
      (node (ref "X43") (pin "1") (pinfunction "1_1") (pintype "passive"))
      (node (ref "X43") (pin "2") (pinfunction "2_2") (pintype "passive"))
      (node (ref "X8") (pin "12") (pinfunction "GND_12") (pintype "passive"))
      (node (ref "X9") (pin "12") (pinfunction "GND_12") (pintype "passive"))
    )
    (net (code "74") (name "V_LED") (class "Default")
      (node (ref "X1") (pin "4") (pinfunction "R1_5_4") (pintype "passive"))
      (node (ref "X1") (pin "9") (pinfunction "R1_2_9") (pintype "passive"))
      (node (ref "X20") (pin "2") (pinfunction "1_2") (pintype "passive"))
    )
    (net (code "75") (name "V_MB") (class "Default")
      (node (ref "X1") (pin "13") (pinfunction "+5_13") (pintype "passive"))
      (node (ref "X14") (pin "13") (pinfunction "+5_13") (pintype "passive"))
      (node (ref "X15") (pin "13") (pinfunction "+5_13") (pintype "passive"))
      (node (ref "X2") (pin "13") (pinfunction "+5_13") (pintype "passive"))
      (node (ref "X20") (pin "1") (pinfunction "0_1") (pintype "passive"))
      (node (ref "X22") (pin "13") (pinfunction "+5_13") (pintype "passive"))
      (node (ref "X23") (pin "13") (pinfunction "+5_13") (pintype "passive"))
      (node (ref "X36") (pin "7") (pinfunction "7_7") (pintype "passive"))
      (node (ref "X8") (pin "13") (pinfunction "+5_13") (pintype "passive"))
      (node (ref "X9") (pin "13") (pinfunction "+5_13") (pintype "passive"))
    )
    (net (code "76") (name "V_RESERVE") (class "Default")
      (node (ref "X20") (pin "3") (pinfunction "2_3") (pintype "passive"))
      (node (ref "X21") (pin "1") (pinfunction "1_1") (pintype "passive"))
    )
    (net (code "77") (name "unconnected-(X1-R2_5-Pad1)") (class "Default")
      (node (ref "X1") (pin "1") (pinfunction "R2_5_1") (pintype "passive"))
    )
    (net (code "78") (name "unconnected-(X1-R2_6-Pad2)") (class "Default")
      (node (ref "X1") (pin "2") (pinfunction "R2_6_2") (pintype "passive"))
    )
    (net (code "79") (name "unconnected-(X1-R2_7-Pad3)") (class "Default")
      (node (ref "X1") (pin "3") (pinfunction "R2_7_3") (pintype "passive"))
    )
    (net (code "80") (name "unconnected-(X2-R1_5-Pad4)") (class "Default")
      (node (ref "X2") (pin "4") (pinfunction "R1_5_4") (pintype "passive"))
    )
    (net (code "81") (name "unconnected-(X2-R1_6-Pad5)") (class "Default")
      (node (ref "X2") (pin "5") (pinfunction "R1_6_5") (pintype "passive"))
    )
    (net (code "82") (name "unconnected-(X2-R1_7-Pad6)") (class "Default")
      (node (ref "X2") (pin "6") (pinfunction "R1_7_6") (pintype "passive"))
    )
    (net (code "83") (name "unconnected-(X2-R2_5-Pad1)") (class "Default")
      (node (ref "X2") (pin "1") (pinfunction "R2_5_1") (pintype "passive"))
    )
    (net (code "84") (name "unconnected-(X2-R2_6-Pad2)") (class "Default")
      (node (ref "X2") (pin "2") (pinfunction "R2_6_2") (pintype "passive"))
    )
    (net (code "85") (name "unconnected-(X2-R2_7-Pad3)") (class "Default")
      (node (ref "X2") (pin "3") (pinfunction "R2_7_3") (pintype "passive"))
    )
    (net (code "86") (name "unconnected-(X8-R1_5-Pad4)") (class "Default")
      (node (ref "X8") (pin "4") (pinfunction "R1_5_4") (pintype "passive"))
    )
    (net (code "87") (name "unconnected-(X8-R1_6-Pad5)") (class "Default")
      (node (ref "X8") (pin "5") (pinfunction "R1_6_5") (pintype "passive"))
    )
    (net (code "88") (name "unconnected-(X8-R1_7-Pad6)") (class "Default")
      (node (ref "X8") (pin "6") (pinfunction "R1_7_6") (pintype "passive"))
    )
    (net (code "89") (name "unconnected-(X8-R2_5-Pad1)") (class "Default")
      (node (ref "X8") (pin "1") (pinfunction "R2_5_1") (pintype "passive"))
    )
    (net (code "90") (name "unconnected-(X8-R2_6-Pad2)") (class "Default")
      (node (ref "X8") (pin "2") (pinfunction "R2_6_2") (pintype "passive"))
    )
    (net (code "91") (name "unconnected-(X8-R2_7-Pad3)") (class "Default")
      (node (ref "X8") (pin "3") (pinfunction "R2_7_3") (pintype "passive"))
    )
    (net (code "92") (name "unconnected-(X9-R1_5-Pad4)") (class "Default")
      (node (ref "X9") (pin "4") (pinfunction "R1_5_4") (pintype "passive"))
    )
    (net (code "93") (name "unconnected-(X9-R1_6-Pad5)") (class "Default")
      (node (ref "X9") (pin "5") (pinfunction "R1_6_5") (pintype "passive"))
    )
    (net (code "94") (name "unconnected-(X9-R1_7-Pad6)") (class "Default")
      (node (ref "X9") (pin "6") (pinfunction "R1_7_6") (pintype "passive"))
    )
    (net (code "95") (name "unconnected-(X9-R2_5-Pad1)") (class "Default")
      (node (ref "X9") (pin "1") (pinfunction "R2_5_1") (pintype "passive"))
    )
    (net (code "96") (name "unconnected-(X9-R2_6-Pad2)") (class "Default")
      (node (ref "X9") (pin "2") (pinfunction "R2_6_2") (pintype "passive"))
    )
    (net (code "97") (name "unconnected-(X9-R2_7-Pad3)") (class "Default")
      (node (ref "X9") (pin "3") (pinfunction "R2_7_3") (pintype "passive"))
    )
    (net (code "98") (name "unconnected-(X14-R1_5-Pad4)") (class "Default")
      (node (ref "X14") (pin "4") (pinfunction "R1_5_4") (pintype "passive"))
    )
    (net (code "99") (name "unconnected-(X14-R1_6-Pad5)") (class "Default")
      (node (ref "X14") (pin "5") (pinfunction "R1_6_5") (pintype "passive"))
    )
    (net (code "100") (name "unconnected-(X14-R1_7-Pad6)") (class "Default")
      (node (ref "X14") (pin "6") (pinfunction "R1_7_6") (pintype "passive"))
    )
    (net (code "101") (name "unconnected-(X14-R2_5-Pad1)") (class "Default")
      (node (ref "X14") (pin "1") (pinfunction "R2_5_1") (pintype "passive"))
    )
    (net (code "102") (name "unconnected-(X14-R2_6-Pad2)") (class "Default")
      (node (ref "X14") (pin "2") (pinfunction "R2_6_2") (pintype "passive"))
    )
    (net (code "103") (name "unconnected-(X14-R2_7-Pad3)") (class "Default")
      (node (ref "X14") (pin "3") (pinfunction "R2_7_3") (pintype "passive"))
    )
    (net (code "104") (name "unconnected-(X15-R1_5-Pad4)") (class "Default")
      (node (ref "X15") (pin "4") (pinfunction "R1_5_4") (pintype "passive"))
    )
    (net (code "105") (name "unconnected-(X15-R1_6-Pad5)") (class "Default")
      (node (ref "X15") (pin "5") (pinfunction "R1_6_5") (pintype "passive"))
    )
    (net (code "106") (name "unconnected-(X15-R1_7-Pad6)") (class "Default")
      (node (ref "X15") (pin "6") (pinfunction "R1_7_6") (pintype "passive"))
    )
    (net (code "107") (name "unconnected-(X15-R2_5-Pad1)") (class "Default")
      (node (ref "X15") (pin "1") (pinfunction "R2_5_1") (pintype "passive"))
    )
    (net (code "108") (name "unconnected-(X15-R2_6-Pad2)") (class "Default")
      (node (ref "X15") (pin "2") (pinfunction "R2_6_2") (pintype "passive"))
    )
    (net (code "109") (name "unconnected-(X15-R2_7-Pad3)") (class "Default")
      (node (ref "X15") (pin "3") (pinfunction "R2_7_3") (pintype "passive"))
    )
    (net (code "110") (name "unconnected-(X22-R1_5-Pad4)") (class "Default")
      (node (ref "X22") (pin "4") (pinfunction "R1_5_4") (pintype "passive"))
    )
    (net (code "111") (name "unconnected-(X22-R1_6-Pad5)") (class "Default")
      (node (ref "X22") (pin "5") (pinfunction "R1_6_5") (pintype "passive"))
    )
    (net (code "112") (name "unconnected-(X22-R1_7-Pad6)") (class "Default")
      (node (ref "X22") (pin "6") (pinfunction "R1_7_6") (pintype "passive"))
    )
    (net (code "113") (name "unconnected-(X22-R2_5-Pad1)") (class "Default")
      (node (ref "X22") (pin "1") (pinfunction "R2_5_1") (pintype "passive"))
    )
    (net (code "114") (name "unconnected-(X22-R2_6-Pad2)") (class "Default")
      (node (ref "X22") (pin "2") (pinfunction "R2_6_2") (pintype "passive"))
    )
    (net (code "115") (name "unconnected-(X22-R2_7-Pad3)") (class "Default")
      (node (ref "X22") (pin "3") (pinfunction "R2_7_3") (pintype "passive"))
    )
    (net (code "116") (name "unconnected-(X23-R1_5-Pad4)") (class "Default")
      (node (ref "X23") (pin "4") (pinfunction "R1_5_4") (pintype "passive"))
    )
    (net (code "117") (name "unconnected-(X23-R1_6-Pad5)") (class "Default")
      (node (ref "X23") (pin "5") (pinfunction "R1_6_5") (pintype "passive"))
    )
    (net (code "118") (name "unconnected-(X23-R1_7-Pad6)") (class "Default")
      (node (ref "X23") (pin "6") (pinfunction "R1_7_6") (pintype "passive"))
    )
    (net (code "119") (name "unconnected-(X23-R2_5-Pad1)") (class "Default")
      (node (ref "X23") (pin "1") (pinfunction "R2_5_1") (pintype "passive"))
    )
    (net (code "120") (name "unconnected-(X23-R2_6-Pad2)") (class "Default")
      (node (ref "X23") (pin "2") (pinfunction "R2_6_2") (pintype "passive"))
    )
    (net (code "121") (name "unconnected-(X23-R2_7-Pad3)") (class "Default")
      (node (ref "X23") (pin "3") (pinfunction "R2_7_3") (pintype "passive"))
    )
    (net (code "122") (name "unconnected-(X26-+V-Pad3)") (class "Default")
      (node (ref "X26") (pin "3") (pinfunction "+V_3") (pintype "passive"))
    )
    (net (code "123") (name "unconnected-(X26--V-Pad4)") (class "Default")
      (node (ref "X26") (pin "4") (pinfunction "-V_4") (pintype "passive"))
    )
    (net (code "124") (name "unconnected-(X34-+5V-Pad27)") (class "Default")
      (node (ref "X34") (pin "27") (pinfunction "+5V_27") (pintype "passive"))
    )
    (net (code "125") (name "unconnected-(X34-3V3-Pad17)") (class "Default")
      (node (ref "X34") (pin "17") (pinfunction "3V3_17") (pintype "passive"))
    )
    (net (code "126") (name "unconnected-(X34-A6-Pad25)") (class "Default")
      (node (ref "X34") (pin "25") (pinfunction "A6_25") (pintype "passive"))
    )
    (net (code "127") (name "unconnected-(X34-A7-Pad26)") (class "Default")
      (node (ref "X34") (pin "26") (pinfunction "A7_26") (pintype "passive"))
    )
    (net (code "128") (name "unconnected-(X34-AREF-Pad18)") (class "Default")
      (node (ref "X34") (pin "18") (pinfunction "AREF_18") (pintype "passive"))
    )
    (net (code "129") (name "unconnected-(X34-D6-Pad9)") (class "Default")
      (node (ref "X34") (pin "9") (pinfunction "D6_9") (pintype "passive"))
    )
    (net (code "130") (name "unconnected-(X34-RST-Pad3)") (class "Default")
      (node (ref "X34") (pin "3") (pinfunction "RST_3") (pintype "passive"))
    )
    (net (code "131") (name "unconnected-(X34-RST-Pad28)") (class "Default")
      (node (ref "X34") (pin "28") (pinfunction "RST_28") (pintype "passive"))
    )
    (net (code "132") (name "unconnected-(X34-RX-Pad2)") (class "Default")
      (node (ref "X34") (pin "2") (pinfunction "RX_2") (pintype "passive"))
    )
    (net (code "133") (name "unconnected-(X34-TX-Pad1)") (class "Default")
      (node (ref "X34") (pin "1") (pinfunction "TX_1") (pintype "passive"))
    )
    (net (code "134") (name "unconnected-(X34-VIN-Pad30)") (class "Default")
      (node (ref "X34") (pin "30") (pinfunction "VIN_30") (pintype "passive"))
    )
    (net (code "135") (name "unconnected-(X36-Pad1)") (class "Default")
      (node (ref "X36") (pin "1") (pinfunction "1_1") (pintype "passive"))
    )
    (net (code "136") (name "unconnected-(X36-Pad3)") (class "Default")
      (node (ref "X36") (pin "3") (pinfunction "3_3") (pintype "passive"))
    )
    (net (code "137") (name "unconnected-(X36-Pad4)") (class "Default")
      (node (ref "X36") (pin "4") (pinfunction "4_4") (pintype "passive"))
    )
    (net (code "138") (name "unconnected-(X36-Pad5)") (class "Default")
      (node (ref "X36") (pin "5") (pinfunction "5_5") (pintype "passive"))
    )
    (net (code "139") (name "unconnected-(X36-Pad9)") (class "Default")
      (node (ref "X36") (pin "9") (pinfunction "9_9") (pintype "passive"))
    )
    (net (code "140") (name "unconnected-(X40-VBUS-Pad1)") (class "Default")
      (node (ref "X40") (pin "1") (pinfunction "VBUS_1") (pintype "passive"))
    )
  )
)
